# LeftBar3.net
KiCad netlist of a schematic drawn in Altium Designer
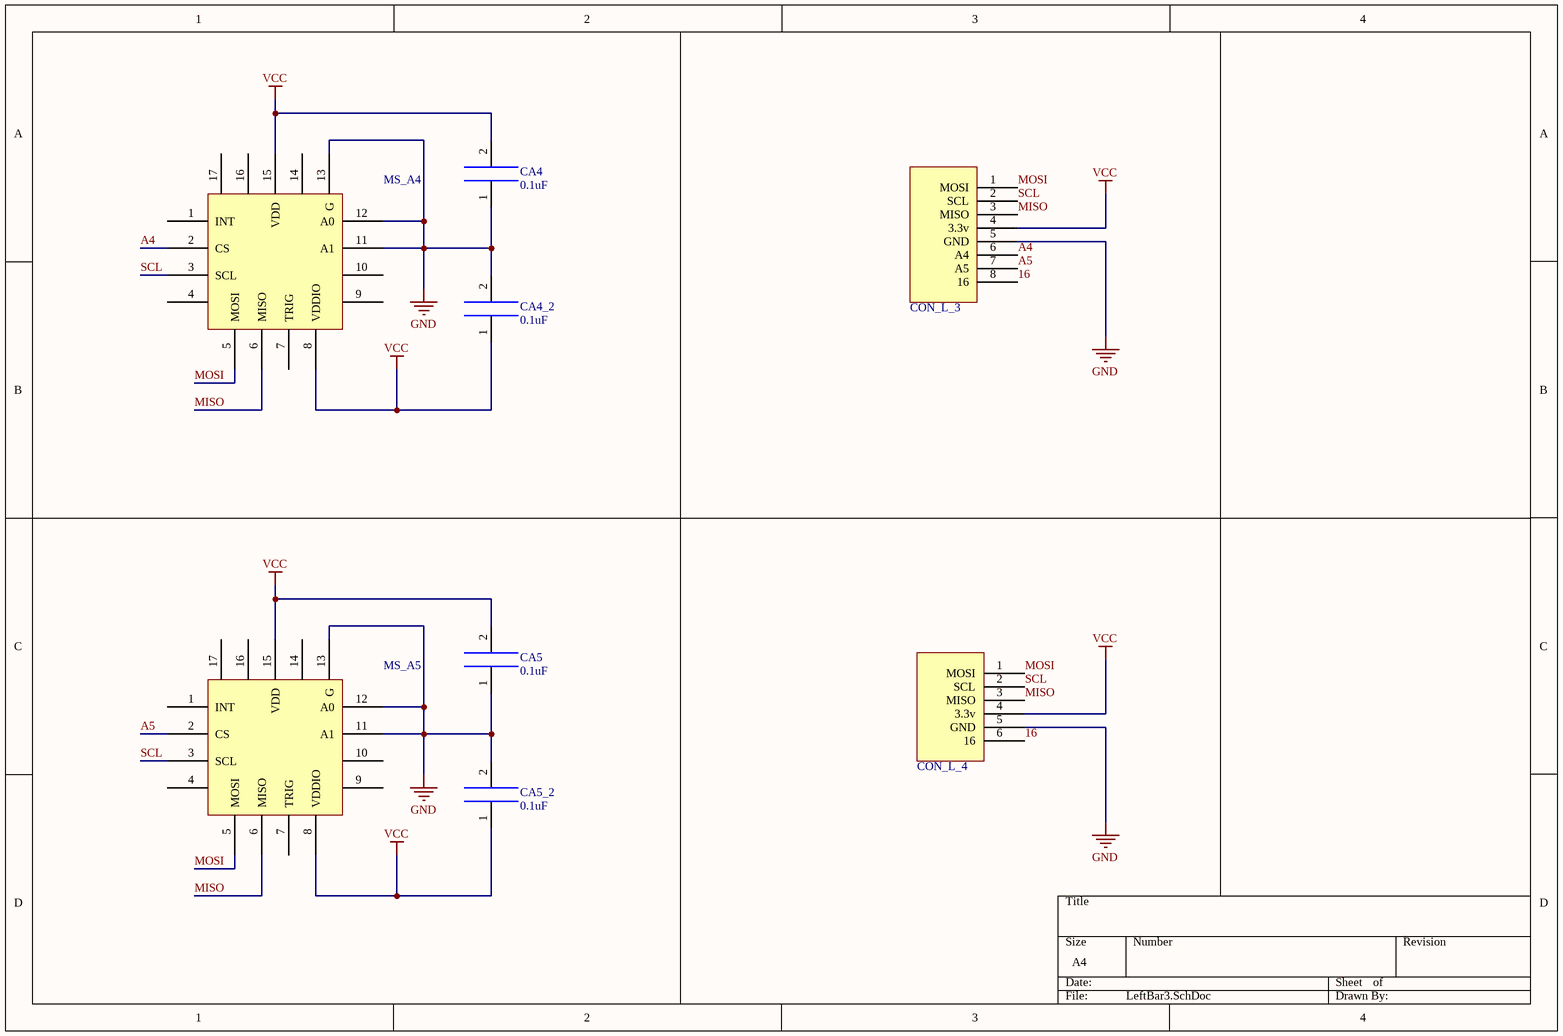
[diagram p0: LeftBar3.SchDoc]

(export (version "E")
  (design (tool "Eeschema 10.0.6"))
  (components
    (comp (ref "CA4")
      (value "0.1uF")
      (footprint "CAP_0603")
      (description "Capacitance")
      (libsource (lib "MagWaySchlib") (part "CAP"))
    )
    (comp (ref "CA4_2")
      (value "0.1uF")
      (footprint "CAP_0603")
      (description "Capacitance")
      (libsource (lib "MagWaySchlib") (part "CAP"))
    )
    (comp (ref "CA5")
      (value "0.1uF")
      (footprint "CAP_0603")
      (description "Capacitance")
      (libsource (lib "MagWaySchlib") (part "CAP"))
    )
    (comp (ref "CA5_2")
      (value "0.1uF")
      (footprint "CAP_0603")
      (description "Capacitance")
      (libsource (lib "MagWaySchlib") (part "CAP"))
    )
    (comp (ref "CON_L_3")
      (value "PIN_left")
      (footprint "PIN_Left_3")
      (libsource (lib "MagWaySchlib") (part "PIN_left_3"))
    )
    (comp (ref "CON_L_4")
      (value "PIN_left")
      (footprint "PIN_Left_4")
      (libsource (lib "MagWaySchlib") (part "PIN_left_4"))
    )
    (comp (ref "MS_A4")
      (value "MLX90393SLW ABA 011 RE")
      (footprint "MLX90393")
      (description "MLX90393 Sensor")
      (libsource (lib "MagWaySchlib") (part "MLX90393SLW ABA 011 RE"))
    )
    (comp (ref "MS_A5")
      (value "MLX90393SLW ABA 011 RE")
      (footprint "MLX90393")
      (description "MLX90393 Sensor")
      (libsource (lib "MagWaySchlib") (part "MLX90393SLW ABA 011 RE"))
    )
  )
  (nets
    (net (code "1") (name "/16") (class "Default")
      (node (ref "CON_L_3") (pin "8") (pinfunction "16_8") (pintype "passive"))
      (node (ref "CON_L_4") (pin "6") (pinfunction "16_6") (pintype "passive"))
    )
    (net (code "2") (name "/A4") (class "Default")
      (node (ref "CON_L_3") (pin "6") (pinfunction "A4_6") (pintype "passive"))
      (node (ref "MS_A4") (pin "2") (pinfunction "CS_2") (pintype "passive"))
    )
    (net (code "3") (name "/A5") (class "Default")
      (node (ref "CON_L_3") (pin "7") (pinfunction "A5_7") (pintype "passive"))
      (node (ref "MS_A5") (pin "2") (pinfunction "CS_2") (pintype "passive"))
    )
    (net (code "4") (name "/MISO") (class "Default")
      (node (ref "CON_L_3") (pin "3") (pinfunction "MISO_3") (pintype "passive"))
      (node (ref "CON_L_4") (pin "3") (pinfunction "MISO_3") (pintype "passive"))
      (node (ref "MS_A4") (pin "6") (pinfunction "MISO_6") (pintype "passive"))
      (node (ref "MS_A5") (pin "6") (pinfunction "MISO_6") (pintype "passive"))
    )
    (net (code "5") (name "/MOSI") (class "Default")
      (node (ref "CON_L_3") (pin "1") (pinfunction "MOSI_1") (pintype "passive"))
      (node (ref "CON_L_4") (pin "1") (pinfunction "MOSI_1") (pintype "passive"))
      (node (ref "MS_A4") (pin "5") (pinfunction "MOSI_5") (pintype "passive"))
      (node (ref "MS_A5") (pin "5") (pinfunction "MOSI_5") (pintype "passive"))
    )
    (net (code "6") (name "/SCL") (class "Default")
      (node (ref "CON_L_3") (pin "2") (pinfunction "SCL_2") (pintype "passive"))
      (node (ref "CON_L_4") (pin "2") (pinfunction "SCL_2") (pintype "passive"))
      (node (ref "MS_A4") (pin "3") (pinfunction "SCL_3") (pintype "passive"))
      (node (ref "MS_A5") (pin "3") (pinfunction "SCL_3") (pintype "passive"))
    )
    (net (code "7") (name "GND") (class "Default")
      (node (ref "CA4") (pin "1") (pintype "passive"))
      (node (ref "CA4_2") (pin "2") (pintype "passive"))
      (node (ref "CA5") (pin "1") (pintype "passive"))
      (node (ref "CA5_2") (pin "2") (pintype "passive"))
      (node (ref "CON_L_3") (pin "5") (pinfunction "GND_5") (pintype "passive"))
      (node (ref "CON_L_4") (pin "5") (pinfunction "GND_5") (pintype "passive"))
      (node (ref "MS_A4") (pin "11") (pinfunction "A1_11") (pintype "passive"))
      (node (ref "MS_A4") (pin "12") (pinfunction "A0_12") (pintype "passive"))
      (node (ref "MS_A4") (pin "13") (pinfunction "G_13") (pintype "passive"))
      (node (ref "MS_A5") (pin "11") (pinfunction "A1_11") (pintype "passive"))
      (node (ref "MS_A5") (pin "12") (pinfunction "A0_12") (pintype "passive"))
      (node (ref "MS_A5") (pin "13") (pinfunction "G_13") (pintype "passive"))
    )
    (net (code "8") (name "VCC") (class "Default")
      (node (ref "CA4") (pin "2") (pintype "passive"))
      (node (ref "CA4_2") (pin "1") (pintype "passive"))
      (node (ref "CA5") (pin "2") (pintype "passive"))
      (node (ref "CA5_2") (pin "1") (pintype "passive"))
      (node (ref "CON_L_3") (pin "4") (pinfunction "3.3v_4") (pintype "passive"))
      (node (ref "CON_L_4") (pin "4") (pinfunction "3.3v_4") (pintype "passive"))
      (node (ref "MS_A4") (pin "15") (pinfunction "VDD_15") (pintype "passive"))
      (node (ref "MS_A4") (pin "8") (pinfunction "VDDIO_8") (pintype "passive"))
      (node (ref "MS_A5") (pin "15") (pinfunction "VDD_15") (pintype "passive"))
      (node (ref "MS_A5") (pin "8") (pinfunction "VDDIO_8") (pintype "passive"))
    )
    (net (code "9") (name "unconnected-(MS_A4-INT-Pad1)") (class "Default")
      (node (ref "MS_A4") (pin "1") (pinfunction "INT_1") (pintype "passive"))
    )
    (net (code "10") (name "unconnected-(MS_A4-Pad4)") (class "Default")
      (node (ref "MS_A4") (pin "4") (pintype "passive"))
    )
    (net (code "11") (name "unconnected-(MS_A4-Pad9)") (class "Default")
      (node (ref "MS_A4") (pin "9") (pintype "passive"))
    )
    (net (code "12") (name "unconnected-(MS_A4-Pad10)") (class "Default")
      (node (ref "MS_A4") (pin "10") (pintype "passive"))
    )
    (net (code "13") (name "unconnected-(MS_A4-Pad14)") (class "Default")
      (node (ref "MS_A4") (pin "14") (pintype "passive"))
    )
    (net (code "14") (name "unconnected-(MS_A4-Pad16)") (class "Default")
      (node (ref "MS_A4") (pin "16") (pintype "passive"))
    )
    (net (code "15") (name "unconnected-(MS_A4-Pad17)") (class "Default")
      (node (ref "MS_A4") (pin "17") (pintype "passive"))
    )
    (net (code "16") (name "unconnected-(MS_A4-TRIG-Pad7)") (class "Default")
      (node (ref "MS_A4") (pin "7") (pinfunction "TRIG_7") (pintype "passive"))
    )
    (net (code "17") (name "unconnected-(MS_A5-INT-Pad1)") (class "Default")
      (node (ref "MS_A5") (pin "1") (pinfunction "INT_1") (pintype "passive"))
    )
    (net (code "18") (name "unconnected-(MS_A5-Pad4)") (class "Default")
      (node (ref "MS_A5") (pin "4") (pintype "passive"))
    )
    (net (code "19") (name "unconnected-(MS_A5-Pad9)") (class "Default")
      (node (ref "MS_A5") (pin "9") (pintype "passive"))
    )
    (net (code "20") (name "unconnected-(MS_A5-Pad10)") (class "Default")
      (node (ref "MS_A5") (pin "10") (pintype "passive"))
    )
    (net (code "21") (name "unconnected-(MS_A5-Pad14)") (class "Default")
      (node (ref "MS_A5") (pin "14") (pintype "passive"))
    )
    (net (code "22") (name "unconnected-(MS_A5-Pad16)") (class "Default")
      (node (ref "MS_A5") (pin "16") (pintype "passive"))
    )
    (net (code "23") (name "unconnected-(MS_A5-Pad17)") (class "Default")
      (node (ref "MS_A5") (pin "17") (pintype "passive"))
    )
    (net (code "24") (name "unconnected-(MS_A5-TRIG-Pad7)") (class "Default")
      (node (ref "MS_A5") (pin "7") (pinfunction "TRIG_7") (pintype "passive"))
    )
  )
)
